# 07_Buzzer.net
KiCad netlist of a schematic drawn in Altium Designer
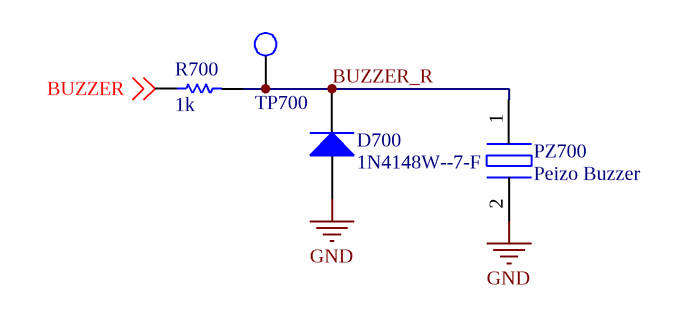
[diagram p0: 07_Buzzer.SchDoc]

(export (version "E")
  (design (tool "Eeschema 10.0.6"))
  (components
    (comp (ref "D700")
      (value "DIODE_4148")
      (footprint "SOD323-12")
      (description "DIODE GEN PURP 100V 300MA SOD123")
      (fields (field (name "MANUFACTURER") "Diodes") (field (name "MANUFACTURER PART NUMBER") "1N4148W--7-F"))
      (libsource (lib "ece315-2017-fall") (part "DIODE_4148"))
    )
    (comp (ref "PZ700")
      (value "Peizo Buzzer")
      (footprint "PKLCS")
      (description "AUDIO PIEZO TRANSDUCER 12.5V SMD")
      (fields
        (field (name "MANUFACTURER PART NUMBER") "PKLCS1212E2000-R1")
        (field (name "MANUFACTURER") "Murata Electronics North America")
      )
      (libsource (lib "ece315-2017-fall") (part "Peizo"))
    )
    (comp (ref "R700")
      (value "RES_0805_K_001.00")
      (footprint "RES_0805")
      (description "RES SMD 1K OHM 1% 1/8W 0805")
      (fields
        (field (name "MANUFACTURER PART NUMBER") "ERJ-6ENF1001V")
        (field (name "TOLERANCE") "±1%")
        (field (name "RESISTANCE (OHMS)") "1k")
      )
      (libsource (lib "ece315-2017-fall") (part "RES_0805_K_001.00"))
    )
    (comp (ref "TP700")
      (value "TP_1206")
      (footprint "TP-SMC-1206")
      (description "Test Point SMD 1206")
      (fields
        (field (name "MANUFACTURER") "TE Connectivity (Tyco Electronics)")
        (field (name "MANUFACTURER PART NUMBER") "1625854-1")
      )
      (libsource (lib "ece315-2017-fall") (part "TP_1206"))
    )
  )
  (nets
    (net (code "1") (name "/BUZZER_R") (class "Default")
      (node (ref "D700") (pin "1") (pinfunction "K_1") (pintype "passive"))
      (node (ref "PZ700") (pin "1") (pinfunction "In_1") (pintype "passive"))
      (node (ref "R700") (pin "2") (pinfunction "2_2") (pintype "passive"))
      (node (ref "TP700") (pin "1") (pintype "passive"))
    )
    (net (code "2") (name "BUZZER") (class "Default")
      (node (ref "R700") (pin "1") (pinfunction "1_1") (pintype "passive"))
    )
    (net (code "3") (name "GND") (class "Default")
      (node (ref "D700") (pin "2") (pinfunction "A_2") (pintype "passive"))
      (node (ref "PZ700") (pin "2") (pinfunction "In_2") (pintype "passive"))
    )
  )
)
